# Ethernet.net
KiCad netlist of a schematic drawn in Altium Designer
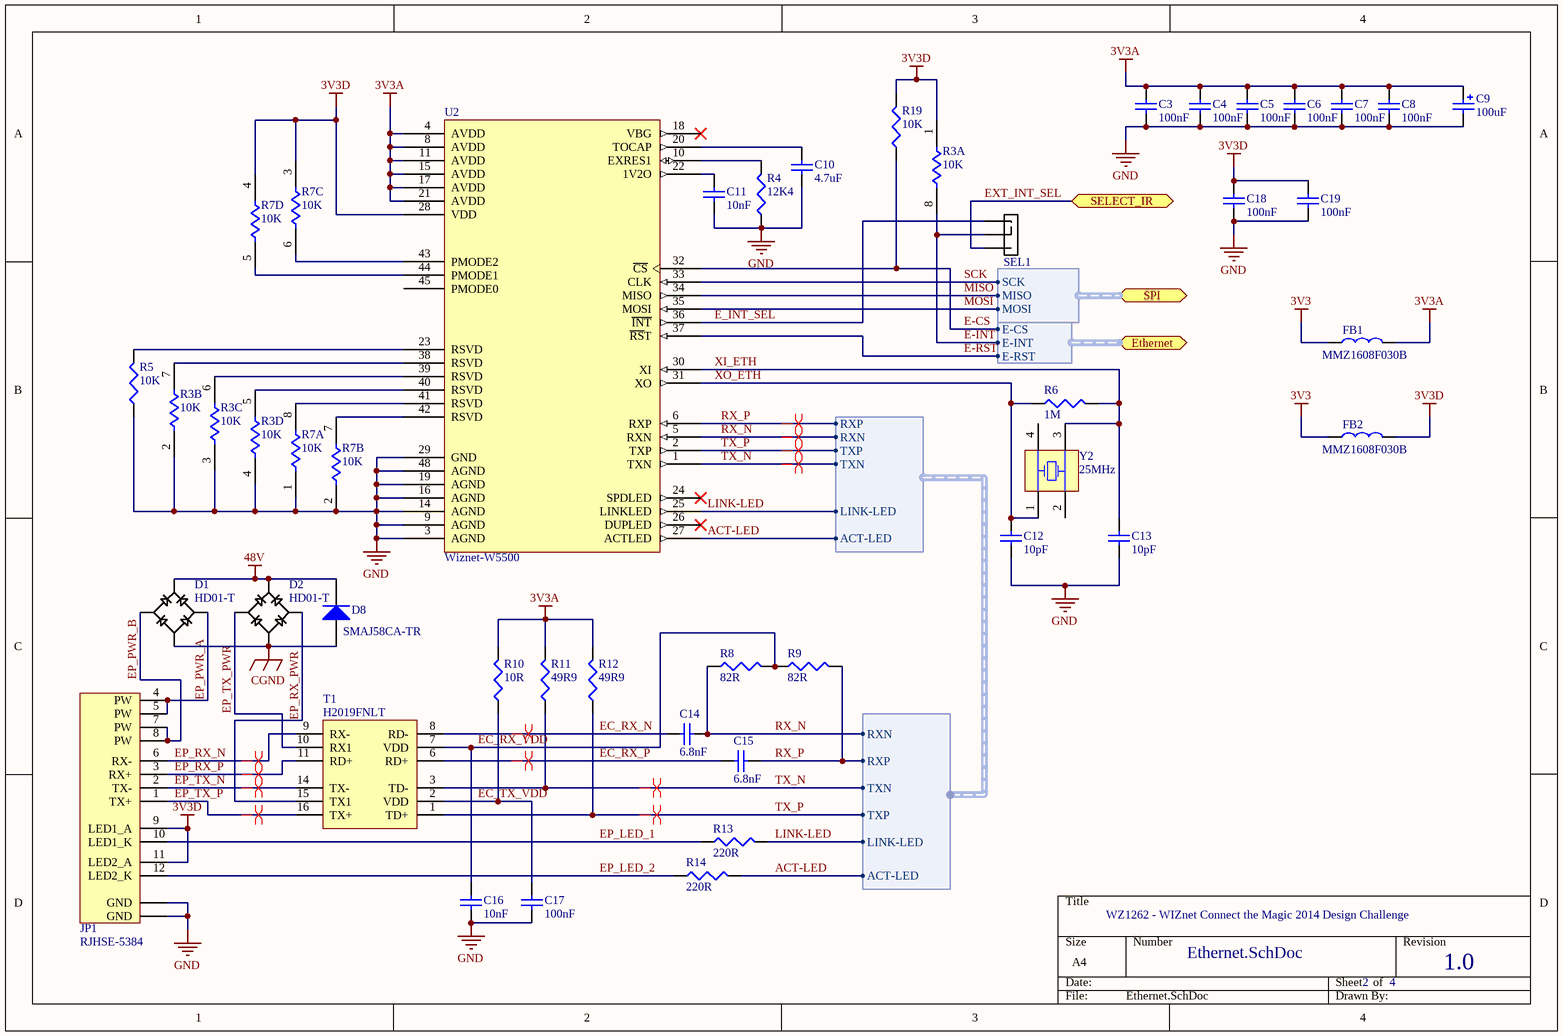
[diagram p0: Ethernet.SchDoc]

(export (version "E")
  (design (tool "Eeschema 10.0.6"))
  (components
    (comp (ref "C3")
      (value "100nF")
      (footprint "0603")
      (description "Capacitor (Semiconductor SIM Model)")
      (fields (field (name "PUBLISHER") "Altium Limited"))
      (libsource (lib "snarc+") (part "Cap_100pF"))
    )
    (comp (ref "C4")
      (value "100nF")
      (footprint "0603")
      (description "Capacitor (Semiconductor SIM Model)")
      (fields (field (name "PUBLISHER") "Altium Limited"))
      (libsource (lib "snarc+") (part "Cap_100pF"))
    )
    (comp (ref "C5")
      (value "100nF")
      (footprint "0603")
      (description "Capacitor (Semiconductor SIM Model)")
      (fields (field (name "PUBLISHER") "Altium Limited"))
      (libsource (lib "snarc+") (part "Cap_100pF"))
    )
    (comp (ref "C6")
      (value "100nF")
      (footprint "0603")
      (description "Capacitor (Semiconductor SIM Model)")
      (fields (field (name "PUBLISHER") "Altium Limited"))
      (libsource (lib "snarc+") (part "Cap_100pF"))
    )
    (comp (ref "C7")
      (value "100nF")
      (footprint "0603")
      (description "Capacitor (Semiconductor SIM Model)")
      (fields (field (name "PUBLISHER") "Altium Limited"))
      (libsource (lib "snarc+") (part "Cap_100pF"))
    )
    (comp (ref "C8")
      (value "100nF")
      (footprint "0603")
      (description "Capacitor (Semiconductor SIM Model)")
      (fields (field (name "PUBLISHER") "Altium Limited"))
      (libsource (lib "snarc+") (part "Cap_100pF"))
    )
    (comp (ref "C9")
      (value "100uF")
      (footprint "PANASONIC_C")
      (description "Polarized Capacitor (Surface Mount)")
      (fields (field (name "PUBLISHER") "Altium Limited"))
      (libsource (lib "snarc+") (part "Cap_Polarized_100uF"))
    )
    (comp (ref "C10")
      (value "4.7uF")
      (footprint "0603")
      (description "Capacitor (Semiconductor SIM Model)")
      (fields (field (name "PUBLISHER") "Altium Limited"))
      (libsource (lib "snarc+") (part "Cap_4.7uF"))
    )
    (comp (ref "C11")
      (value "10nF")
      (footprint "0603")
      (description "Capacitor (Semiconductor SIM Model)")
      (fields (field (name "PUBLISHER") "Altium Limited"))
      (libsource (lib "snarc+") (part "Cap_10nF"))
    )
    (comp (ref "C12")
      (value "10pF")
      (footprint "0603")
      (description "Capacitor (Semiconductor SIM Model)")
      (fields (field (name "PUBLISHER") "Altium Limited"))
      (libsource (lib "snarc+") (part "Cap_10pF"))
    )
    (comp (ref "C13")
      (value "10pF")
      (footprint "0603")
      (description "Capacitor (Semiconductor SIM Model)")
      (fields (field (name "PUBLISHER") "Altium Limited"))
      (libsource (lib "snarc+") (part "Cap_10pF"))
    )
    (comp (ref "C14")
      (value "6.8nF")
      (footprint "0603")
      (description "Capacitor (Semiconductor SIM Model)")
      (fields (field (name "PUBLISHER") "Altium Limited"))
      (libsource (lib "snarc+") (part "Cap_6.8nF"))
    )
    (comp (ref "C15")
      (value "6.8nF")
      (footprint "0603")
      (description "Capacitor (Semiconductor SIM Model)")
      (fields (field (name "PUBLISHER") "Altium Limited"))
      (libsource (lib "snarc+") (part "Cap_6.8nF"))
    )
    (comp (ref "C16")
      (value "10nF")
      (footprint "0603")
      (description "Capacitor (Semiconductor SIM Model)")
      (fields (field (name "PUBLISHER") "Altium Limited"))
      (libsource (lib "snarc+") (part "Cap_10nF"))
    )
    (comp (ref "C17")
      (value "100nF")
      (footprint "0603")
      (description "Capacitor (Semiconductor SIM Model)")
      (fields (field (name "PUBLISHER") "Altium Limited"))
      (libsource (lib "snarc+") (part "Cap_100nF"))
    )
    (comp (ref "C18")
      (value "100nF")
      (footprint "0603")
      (description "Capacitor (Semiconductor SIM Model)")
      (fields (field (name "PUBLISHER") "Altium Limited"))
      (libsource (lib "snarc+") (part "Cap_100pF"))
    )
    (comp (ref "C19")
      (value "100nF")
      (footprint "0603")
      (description "Capacitor (Semiconductor SIM Model)")
      (fields (field (name "PUBLISHER") "Altium Limited"))
      (libsource (lib "snarc+") (part "Cap_100pF"))
    )
    (comp (ref "D1")
      (value "HD01-T")
      (footprint "MBS")
      (description "Diode Bridge")
      (fields (field (name "PUBLISHER") "Altium Limited"))
      (libsource (lib "snarc+") (part "Diode Bridge"))
    )
    (comp (ref "D2")
      (value "HD01-T")
      (footprint "MBS")
      (description "Diode Bridge")
      (fields (field (name "PUBLISHER") "Altium Limited"))
      (libsource (lib "snarc+") (part "Diode Bridge"))
    )
    (comp (ref "D8")
      (value "SMAJ58CA-TR")
      (footprint "SMBJ")
      (description "Default Diode")
      (fields (field (name "PUBLISHER") "Altium Limited"))
      (libsource (lib "snarc+") (part "Diode_POWER"))
    )
    (comp (ref "FB1")
      (value "MMZ1608F030B")
      (footprint "0603")
      (description "Ferrite Bead")
      (fields (field (name "PUBLISHER") "Altium Limited"))
      (libsource (lib "NetTroll") (part "Ferrite Bead"))
    )
    (comp (ref "FB2")
      (value "MMZ1608F030B")
      (footprint "0603")
      (description "Ferrite Bead")
      (fields (field (name "PUBLISHER") "Altium Limited"))
      (libsource (lib "NetTroll") (part "Ferrite Bead"))
    )
    (comp (ref "JP1")
      (value "RJHSE-5384")
      (footprint "RJHSE-5484")
      (description "Ethernet Socket RJ45 With Leds")
      (libsource (lib "snarc+") (part "Ethernet Socket"))
    )
    (comp (ref "R3")
      (value "10K")
      (footprint "SO8_S")
      (description "Isolated Resistor Network - Parts")
      (fields (field (name "PUBLISHER") "Altium Limited"))
      (libsource (lib "snarc+") (part "Resistor_Pack_10K"))
    )
    (comp (ref "R4")
      (value "12K4")
      (footprint "0603")
      (description "Resistor")
      (fields (field (name "PUBLISHER") "Altium Limited"))
      (libsource (lib "snarc+") (part "Resistor_12K4"))
    )
    (comp (ref "R5")
      (value "10K")
      (footprint "0603")
      (description "Resistor")
      (fields (field (name "PUBLISHER") "Altium Limited"))
      (libsource (lib "snarc+") (part "Resistor_10K"))
    )
    (comp (ref "R6")
      (value "1M")
      (footprint "0603")
      (description "Resistor")
      (fields (field (name "PUBLISHER") "Altium Limited"))
      (libsource (lib "snarc+") (part "Resistor_1M"))
    )
    (comp (ref "R7")
      (value "10K")
      (footprint "SO8_S")
      (description "Isolated Resistor Network - Parts")
      (fields (field (name "PUBLISHER") "Altium Limited"))
      (libsource (lib "snarc+") (part "Resistor_Pack_10K"))
    )
    (comp (ref "R8")
      (value "82R")
      (footprint "0603")
      (description "Resistor")
      (fields (field (name "PUBLISHER") "Altium Limited"))
      (libsource (lib "snarc+") (part "Resistor_82R"))
    )
    (comp (ref "R9")
      (value "82R")
      (footprint "0603")
      (description "Resistor")
      (fields (field (name "PUBLISHER") "Altium Limited"))
      (libsource (lib "snarc+") (part "Resistor_82R"))
    )
    (comp (ref "R10")
      (value "10R")
      (footprint "0603")
      (description "Resistor")
      (fields (field (name "PUBLISHER") "Altium Limited"))
      (libsource (lib "snarc+") (part "Resistor_10R"))
    )
    (comp (ref "R11")
      (value "49R9")
      (footprint "0603")
      (description "Resistor")
      (fields (field (name "PUBLISHER") "Altium Limited"))
      (libsource (lib "snarc+") (part "Resistor_49R9"))
    )
    (comp (ref "R12")
      (value "49R9")
      (footprint "0603")
      (description "Resistor")
      (fields (field (name "PUBLISHER") "Altium Limited"))
      (libsource (lib "snarc+") (part "Resistor_49R9"))
    )
    (comp (ref "R13")
      (value "220R")
      (footprint "0603")
      (description "Resistor")
      (fields (field (name "PUBLISHER") "Altium Limited"))
      (libsource (lib "snarc+") (part "Resistor_220R"))
    )
    (comp (ref "R14")
      (value "220R")
      (footprint "0603")
      (description "Resistor")
      (fields (field (name "PUBLISHER") "Altium Limited"))
      (libsource (lib "snarc+") (part "Resistor_220R"))
    )
    (comp (ref "R19")
      (value "10K")
      (footprint "0603")
      (description "Resistor")
      (fields (field (name "PUBLISHER") "Altium Limited"))
      (libsource (lib "snarc+") (part "Resistor_10K"))
    )
    (comp (ref "SEL1")
      (value "SELECTOR")
      (footprint "SJ_3_PASTE2&3")
      (description "Solder Selector")
      (libsource (lib "snarc+3") (part "SELECTOR"))
    )
    (comp (ref "T1")
      (value "H2019FNLT")
      (footprint "HXXXX")
      (description "Power over Ethernet Magnetic Module")
      (fields (field (name "PUBLISHER") "Altium Limited"))
      (libsource (lib "snarc+3") (part "Magnetics"))
    )
    (comp (ref "U2")
      (value "Wiznet-W5500")
      (footprint "QFN48")
      (description "W5500 Fast SPI Ethernet Controller")
      (libsource (lib "snarc+3") (part "Wiznet-W5500"))
    )
    (comp (ref "Y2")
      (value "25MHz")
      (footprint "CRYSTAL-SMD-2.5X2-ABM10")
      (description "Surface Mount Quartz Crystal")
      (fields (field (name "PUBLISHER") "Altium Limited"))
      (libsource (lib "snarc+") (part "Crystal_25MHz"))
    )
  )
  (nets
    (net (code "4") (name "/ACT-LED") (class "Default")
      (node (ref "R14") (pin "2") (pinfunction "2_2") (pintype "passive"))
      (node (ref "U2") (pin "27") (pinfunction "ACTLED_27") (pintype "output"))
    )
    (net (code "5") (name "/E-CS") (class "Default")
      (node (ref "R19") (pin "1") (pinfunction "1_1") (pintype "passive"))
      (node (ref "U2") (pin "32") (pinfunction "~{CS}_32") (pintype "passive"))
    )
    (net (code "6") (name "/E-INT") (class "Default")
      (node (ref "R3") (pin "8") (pinfunction "8_8") (pintype "passive"))
      (node (ref "SEL1") (pin "2") (pinfunction "2_2") (pintype "passive"))
    )
    (net (code "7") (name "/E-RST") (class "Default")
      (node (ref "U2") (pin "37") (pinfunction "~{RS}T_37") (pintype "input"))
    )
    (net (code "8") (name "/EC_RX_N") (class "Default")
      (node (ref "C14") (pin "1") (pinfunction "1_1") (pintype "passive"))
      (node (ref "T1") (pin "8") (pinfunction "RD-_8") (pintype "passive"))
    )
    (net (code "9") (name "/EC_RX_P") (class "Default")
      (node (ref "C15") (pin "1") (pinfunction "1_1") (pintype "passive"))
      (node (ref "T1") (pin "6") (pinfunction "RD+_6") (pintype "passive"))
    )
    (net (code "10") (name "/EC_RX_VDD") (class "Default")
      (node (ref "C16") (pin "2") (pinfunction "2_2") (pintype "passive"))
      (node (ref "R8") (pin "2") (pinfunction "2_2") (pintype "passive"))
      (node (ref "R9") (pin "1") (pinfunction "1_1") (pintype "passive"))
      (node (ref "T1") (pin "7") (pinfunction "VDD_7") (pintype "passive"))
    )
    (net (code "11") (name "/EC_TX_VDD") (class "Default")
      (node (ref "C17") (pin "2") (pinfunction "2_2") (pintype "passive"))
      (node (ref "R10") (pin "1") (pinfunction "1_1") (pintype "passive"))
      (node (ref "T1") (pin "2") (pinfunction "VDD_2") (pintype "passive"))
    )
    (net (code "12") (name "/EP_LED_1") (class "Default")
      (node (ref "JP1") (pin "10") (pinfunction "LED1_K_10") (pintype "passive"))
      (node (ref "R13") (pin "1") (pinfunction "1_1") (pintype "passive"))
    )
    (net (code "13") (name "/EP_LED_2") (class "Default")
      (node (ref "JP1") (pin "12") (pinfunction "LED2_K_12") (pintype "passive"))
      (node (ref "R14") (pin "1") (pinfunction "1_1") (pintype "passive"))
    )
    (net (code "14") (name "/EP_PWR_A") (class "Default")
      (node (ref "D1") (pin "AC2") (pinfunction "AC2_AC2") (pintype "power_in"))
      (node (ref "JP1") (pin "4") (pinfunction "PW_4") (pintype "passive"))
      (node (ref "JP1") (pin "5") (pinfunction "PW_5") (pintype "passive"))
    )
    (net (code "15") (name "/EP_PWR_B") (class "Default")
      (node (ref "D1") (pin "AC1") (pinfunction "AC1_AC1") (pintype "power_in"))
      (node (ref "JP1") (pin "7") (pinfunction "PW_7") (pintype "passive"))
      (node (ref "JP1") (pin "8") (pinfunction "PW_8") (pintype "passive"))
    )
    (net (code "16") (name "/EP_RX_N") (class "Default")
      (node (ref "JP1") (pin "6") (pinfunction "RX-_6") (pintype "passive"))
      (node (ref "T1") (pin "9") (pinfunction "RX-_9") (pintype "passive"))
    )
    (net (code "17") (name "/EP_RX_P") (class "Default")
      (node (ref "JP1") (pin "3") (pinfunction "RX+_3") (pintype "passive"))
      (node (ref "T1") (pin "11") (pinfunction "RD+_11") (pintype "passive"))
    )
    (net (code "18") (name "/EP_RX_PWR") (class "Default")
      (node (ref "D2") (pin "AC2") (pinfunction "AC2_AC2") (pintype "power_in"))
      (node (ref "T1") (pin "15") (pinfunction "TX1_15") (pintype "passive"))
    )
    (net (code "19") (name "/EP_TX_N") (class "Default")
      (node (ref "JP1") (pin "2") (pinfunction "TX-_2") (pintype "passive"))
      (node (ref "T1") (pin "14") (pinfunction "TX-_14") (pintype "passive"))
    )
    (net (code "20") (name "/EP_TX_P") (class "Default")
      (node (ref "JP1") (pin "1") (pinfunction "TX+_1") (pintype "passive"))
      (node (ref "T1") (pin "16") (pinfunction "TX+_16") (pintype "passive"))
    )
    (net (code "21") (name "/EP_TX_PWR") (class "Default")
      (node (ref "D2") (pin "AC1") (pinfunction "AC1_AC1") (pintype "power_in"))
      (node (ref "T1") (pin "10") (pinfunction "RX1_10") (pintype "passive"))
    )
    (net (code "22") (name "/EXT_INT_SEL") (class "Default")
      (node (ref "SEL1") (pin "1") (pinfunction "1_1") (pintype "passive"))
    )
    (net (code "23") (name "/E_INT_SEL") (class "Default")
      (node (ref "SEL1") (pin "3") (pinfunction "3_3") (pintype "passive"))
      (node (ref "U2") (pin "36") (pinfunction "~{INT}_36") (pintype "output"))
    )
    (net (code "24") (name "/LINK-LED") (class "Default")
      (node (ref "R13") (pin "2") (pinfunction "2_2") (pintype "passive"))
      (node (ref "U2") (pin "25") (pinfunction "LINKLED_25") (pintype "output"))
    )
    (net (code "25") (name "/MISO") (class "Default")
      (node (ref "U2") (pin "34") (pinfunction "MISO_34") (pintype "output"))
    )
    (net (code "26") (name "/MOSI") (class "Default")
      (node (ref "U2") (pin "35") (pinfunction "MOSI_35") (pintype "input"))
    )
    (net (code "27") (name "/RX_N") (class "Default")
      (node (ref "C14") (pin "2") (pinfunction "2_2") (pintype "passive"))
      (node (ref "R8") (pin "1") (pinfunction "1_1") (pintype "passive"))
      (node (ref "U2") (pin "5") (pinfunction "RXN_5") (pintype "input"))
    )
    (net (code "28") (name "/RX_P") (class "Default")
      (node (ref "C15") (pin "2") (pinfunction "2_2") (pintype "passive"))
      (node (ref "R9") (pin "2") (pinfunction "2_2") (pintype "passive"))
      (node (ref "U2") (pin "6") (pinfunction "RXP_6") (pintype "input"))
    )
    (net (code "29") (name "/SCK") (class "Default")
      (node (ref "U2") (pin "33") (pinfunction "CLK_33") (pintype "input"))
    )
    (net (code "31") (name "/TX_N") (class "Default")
      (node (ref "R11") (pin "1") (pinfunction "1_1") (pintype "passive"))
      (node (ref "T1") (pin "3") (pinfunction "TD-_3") (pintype "passive"))
      (node (ref "U2") (pin "1") (pinfunction "TXN_1") (pintype "output"))
    )
    (net (code "32") (name "/TX_P") (class "Default")
      (node (ref "R12") (pin "1") (pinfunction "1_1") (pintype "passive"))
      (node (ref "T1") (pin "1") (pinfunction "TD+_1") (pintype "passive"))
      (node (ref "U2") (pin "2") (pinfunction "TXP_2") (pintype "output"))
    )
    (net (code "33") (name "/XI_ETH") (class "Default")
      (node (ref "C13") (pin "2") (pinfunction "2_2") (pintype "passive"))
      (node (ref "R6") (pin "2") (pinfunction "2_2") (pintype "passive"))
      (node (ref "U2") (pin "30") (pinfunction "XI_30") (pintype "input"))
      (node (ref "Y2") (pin "3") (pinfunction "OSC2_3") (pintype "passive"))
    )
    (net (code "34") (name "/XO_ETH") (class "Default")
      (node (ref "C12") (pin "2") (pinfunction "2_2") (pintype "passive"))
      (node (ref "R6") (pin "1") (pinfunction "1_1") (pintype "passive"))
      (node (ref "U2") (pin "31") (pinfunction "XO_31") (pintype "output"))
      (node (ref "Y2") (pin "1") (pinfunction "OSC1_1") (pintype "passive"))
    )
    (net (code "37") (name "3V3") (class "Default")
      (node (ref "FB1") (pin "1") (pinfunction "1_1") (pintype "passive"))
      (node (ref "FB2") (pin "1") (pinfunction "1_1") (pintype "passive"))
    )
    (net (code "38") (name "3V3A") (class "Default")
      (node (ref "C3") (pin "2") (pinfunction "2_2") (pintype "passive"))
      (node (ref "C4") (pin "2") (pinfunction "2_2") (pintype "passive"))
      (node (ref "C5") (pin "2") (pinfunction "2_2") (pintype "passive"))
      (node (ref "C6") (pin "2") (pinfunction "2_2") (pintype "passive"))
      (node (ref "C7") (pin "2") (pinfunction "2_2") (pintype "passive"))
      (node (ref "C8") (pin "2") (pinfunction "2_2") (pintype "passive"))
      (node (ref "C9") (pin "+") (pinfunction "+_+") (pintype "passive"))
      (node (ref "FB1") (pin "2") (pinfunction "2_2") (pintype "passive"))
      (node (ref "R10") (pin "2") (pinfunction "2_2") (pintype "passive"))
      (node (ref "R11") (pin "2") (pinfunction "2_2") (pintype "passive"))
      (node (ref "R12") (pin "2") (pinfunction "2_2") (pintype "passive"))
      (node (ref "U2") (pin "11") (pinfunction "AVDD_11") (pintype "power_in"))
      (node (ref "U2") (pin "15") (pinfunction "AVDD_15") (pintype "power_in"))
      (node (ref "U2") (pin "17") (pinfunction "AVDD_17") (pintype "power_in"))
      (node (ref "U2") (pin "21") (pinfunction "AVDD_21") (pintype "power_in"))
      (node (ref "U2") (pin "4") (pinfunction "AVDD_4") (pintype "power_in"))
      (node (ref "U2") (pin "8") (pinfunction "AVDD_8") (pintype "power_in"))
    )
    (net (code "39") (name "3V3D") (class "Default")
      (node (ref "C18") (pin "2") (pinfunction "2_2") (pintype "passive"))
      (node (ref "C19") (pin "2") (pinfunction "2_2") (pintype "passive"))
      (node (ref "FB2") (pin "2") (pinfunction "2_2") (pintype "passive"))
      (node (ref "JP1") (pin "11") (pinfunction "LED2_A_11") (pintype "passive"))
      (node (ref "JP1") (pin "9") (pinfunction "LED1_A_9") (pintype "passive"))
      (node (ref "R19") (pin "2") (pinfunction "2_2") (pintype "passive"))
      (node (ref "R3") (pin "1") (pinfunction "1_1") (pintype "passive"))
      (node (ref "R7") (pin "3") (pinfunction "3_3") (pintype "passive"))
      (node (ref "R7") (pin "4") (pinfunction "4_4") (pintype "passive"))
      (node (ref "U2") (pin "28") (pinfunction "VDD_28") (pintype "power_in"))
    )
    (net (code "40") (name "48V") (class "Default")
      (node (ref "D1") (pin "+") (pinfunction "+_+") (pintype "power_in"))
      (node (ref "D2") (pin "+") (pinfunction "+_+") (pintype "power_in"))
      (node (ref "D8") (pin "2") (pinfunction "K_2") (pintype "passive"))
    )
    (net (code "41") (name "CGND") (class "Default")
      (node (ref "D1") (pin "-") (pinfunction "-_-") (pintype "power_in"))
      (node (ref "D2") (pin "-") (pinfunction "-_-") (pintype "power_in"))
      (node (ref "D8") (pin "1") (pinfunction "A_1") (pintype "passive"))
    )
    (net (code "42") (name "GND") (class "Default")
      (node (ref "C10") (pin "1") (pinfunction "1_1") (pintype "passive"))
      (node (ref "C11") (pin "1") (pinfunction "1_1") (pintype "passive"))
      (node (ref "C12") (pin "1") (pinfunction "1_1") (pintype "passive"))
      (node (ref "C13") (pin "1") (pinfunction "1_1") (pintype "passive"))
      (node (ref "C16") (pin "1") (pinfunction "1_1") (pintype "passive"))
      (node (ref "C17") (pin "1") (pinfunction "1_1") (pintype "passive"))
      (node (ref "C18") (pin "1") (pinfunction "1_1") (pintype "passive"))
      (node (ref "C19") (pin "1") (pinfunction "1_1") (pintype "passive"))
      (node (ref "C3") (pin "1") (pinfunction "1_1") (pintype "passive"))
      (node (ref "C4") (pin "1") (pinfunction "1_1") (pintype "passive"))
      (node (ref "C5") (pin "1") (pinfunction "1_1") (pintype "passive"))
      (node (ref "C6") (pin "1") (pinfunction "1_1") (pintype "passive"))
      (node (ref "C7") (pin "1") (pinfunction "1_1") (pintype "passive"))
      (node (ref "C8") (pin "1") (pinfunction "1_1") (pintype "passive"))
      (node (ref "C9") (pin "-") (pinfunction "-_-") (pintype "passive"))
      (node (ref "JP1") (pin "GND1") (pinfunction "GND_GND1") (pintype "passive"))
      (node (ref "JP1") (pin "GND2") (pinfunction "GND_GND2") (pintype "passive"))
      (node (ref "R3") (pin "2") (pinfunction "2_2") (pintype "passive"))
      (node (ref "R3") (pin "3") (pinfunction "3_3") (pintype "passive"))
      (node (ref "R3") (pin "4") (pinfunction "4_4") (pintype "passive"))
      (node (ref "R4") (pin "1") (pinfunction "1_1") (pintype "passive"))
      (node (ref "R5") (pin "1") (pinfunction "1_1") (pintype "passive"))
      (node (ref "R7") (pin "1") (pinfunction "1_1") (pintype "passive"))
      (node (ref "R7") (pin "2") (pinfunction "2_2") (pintype "passive"))
      (node (ref "U2") (pin "14") (pinfunction "AGND_14") (pintype "power_in"))
      (node (ref "U2") (pin "16") (pinfunction "AGND_16") (pintype "power_in"))
      (node (ref "U2") (pin "19") (pinfunction "AGND_19") (pintype "power_in"))
      (node (ref "U2") (pin "29") (pinfunction "GND_29") (pintype "power_in"))
      (node (ref "U2") (pin "3") (pinfunction "AGND_3") (pintype "power_in"))
      (node (ref "U2") (pin "48") (pinfunction "AGND_48") (pintype "power_in"))
      (node (ref "U2") (pin "9") (pinfunction "AGND_9") (pintype "power_in"))
    )
    (net (code "43") (name "Net-(R3-Pad5)") (class "Default")
      (node (ref "R3") (pin "5") (pinfunction "5_5") (pintype "passive"))
      (node (ref "U2") (pin "40") (pinfunction "RSVD_40") (pintype "power_in"))
    )
    (net (code "44") (name "Net-(R3-Pad6)") (class "Default")
      (node (ref "R3") (pin "6") (pinfunction "6_6") (pintype "passive"))
      (node (ref "U2") (pin "39") (pinfunction "RSVD_39") (pintype "power_in"))
    )
    (net (code "45") (name "Net-(R3-Pad7)") (class "Default")
      (node (ref "R3") (pin "7") (pinfunction "7_7") (pintype "passive"))
      (node (ref "U2") (pin "38") (pinfunction "RSVD_38") (pintype "power_in"))
    )
    (net (code "46") (name "Net-(R5-Pad2)") (class "Default")
      (node (ref "R5") (pin "2") (pinfunction "2_2") (pintype "passive"))
      (node (ref "U2") (pin "23") (pinfunction "RSVD_23") (pintype "power_in"))
    )
    (net (code "47") (name "Net-(R7-Pad7)") (class "Default")
      (node (ref "R7") (pin "7") (pinfunction "7_7") (pintype "passive"))
      (node (ref "U2") (pin "42") (pinfunction "RSVD_42") (pintype "power_in"))
    )
    (net (code "48") (name "Net-(R7-Pad8)") (class "Default")
      (node (ref "R7") (pin "8") (pinfunction "8_8") (pintype "passive"))
      (node (ref "U2") (pin "41") (pinfunction "RSVD_41") (pintype "power_in"))
    )
    (net (code "49") (name "Net-(U2-1V2O)") (class "Default")
      (node (ref "C11") (pin "2") (pinfunction "2_2") (pintype "passive"))
      (node (ref "U2") (pin "22") (pinfunction "1V2O_22") (pintype "output"))
    )
    (net (code "50") (name "Net-(U2-EXRES1)") (class "Default")
      (node (ref "R4") (pin "2") (pinfunction "2_2") (pintype "passive"))
      (node (ref "U2") (pin "10") (pinfunction "EXRES1_10") (pintype "bidirectional"))
    )
    (net (code "51") (name "Net-(U2-PMODE1)") (class "Default")
      (node (ref "R7") (pin "5") (pinfunction "5_5") (pintype "passive"))
      (node (ref "U2") (pin "44") (pinfunction "PMODE1_44") (pintype "power_in"))
    )
    (net (code "52") (name "Net-(U2-PMODE2)") (class "Default")
      (node (ref "R7") (pin "6") (pinfunction "6_6") (pintype "passive"))
      (node (ref "U2") (pin "43") (pinfunction "PMODE2_43") (pintype "power_in"))
    )
    (net (code "53") (name "Net-(U2-TOCAP)") (class "Default")
      (node (ref "C10") (pin "2") (pinfunction "2_2") (pintype "passive"))
      (node (ref "U2") (pin "20") (pinfunction "TOCAP_20") (pintype "output"))
    )
    (net (code "54") (name "unconnected-(U2-DUPLED-Pad26)") (class "Default")
      (node (ref "U2") (pin "26") (pinfunction "DUPLED_26") (pintype "output+no_connect"))
    )
    (net (code "55") (name "unconnected-(U2-PMODE0-Pad45)") (class "Default")
      (node (ref "U2") (pin "45") (pinfunction "PMODE0_45") (pintype "power_in"))
    )
    (net (code "56") (name "unconnected-(U2-SPDLED-Pad24)") (class "Default")
      (node (ref "U2") (pin "24") (pinfunction "SPDLED_24") (pintype "output+no_connect"))
    )
    (net (code "57") (name "unconnected-(U2-VBG-Pad18)") (class "Default")
      (node (ref "U2") (pin "18") (pinfunction "VBG_18") (pintype "output+no_connect"))
    )
    (net (code "58") (name "unconnected-(Y2-OSC1-Pad4)") (class "Default")
      (node (ref "Y2") (pin "4") (pinfunction "OSC1_4") (pintype "passive"))
    )
    (net (code "59") (name "unconnected-(Y2-OSC2-Pad2)") (class "Default")
      (node (ref "Y2") (pin "2") (pinfunction "OSC2_2") (pintype "passive"))
    )
  )
)
